# ZD-STM32.net
KiCad netlist of a schematic drawn in Altium Designer
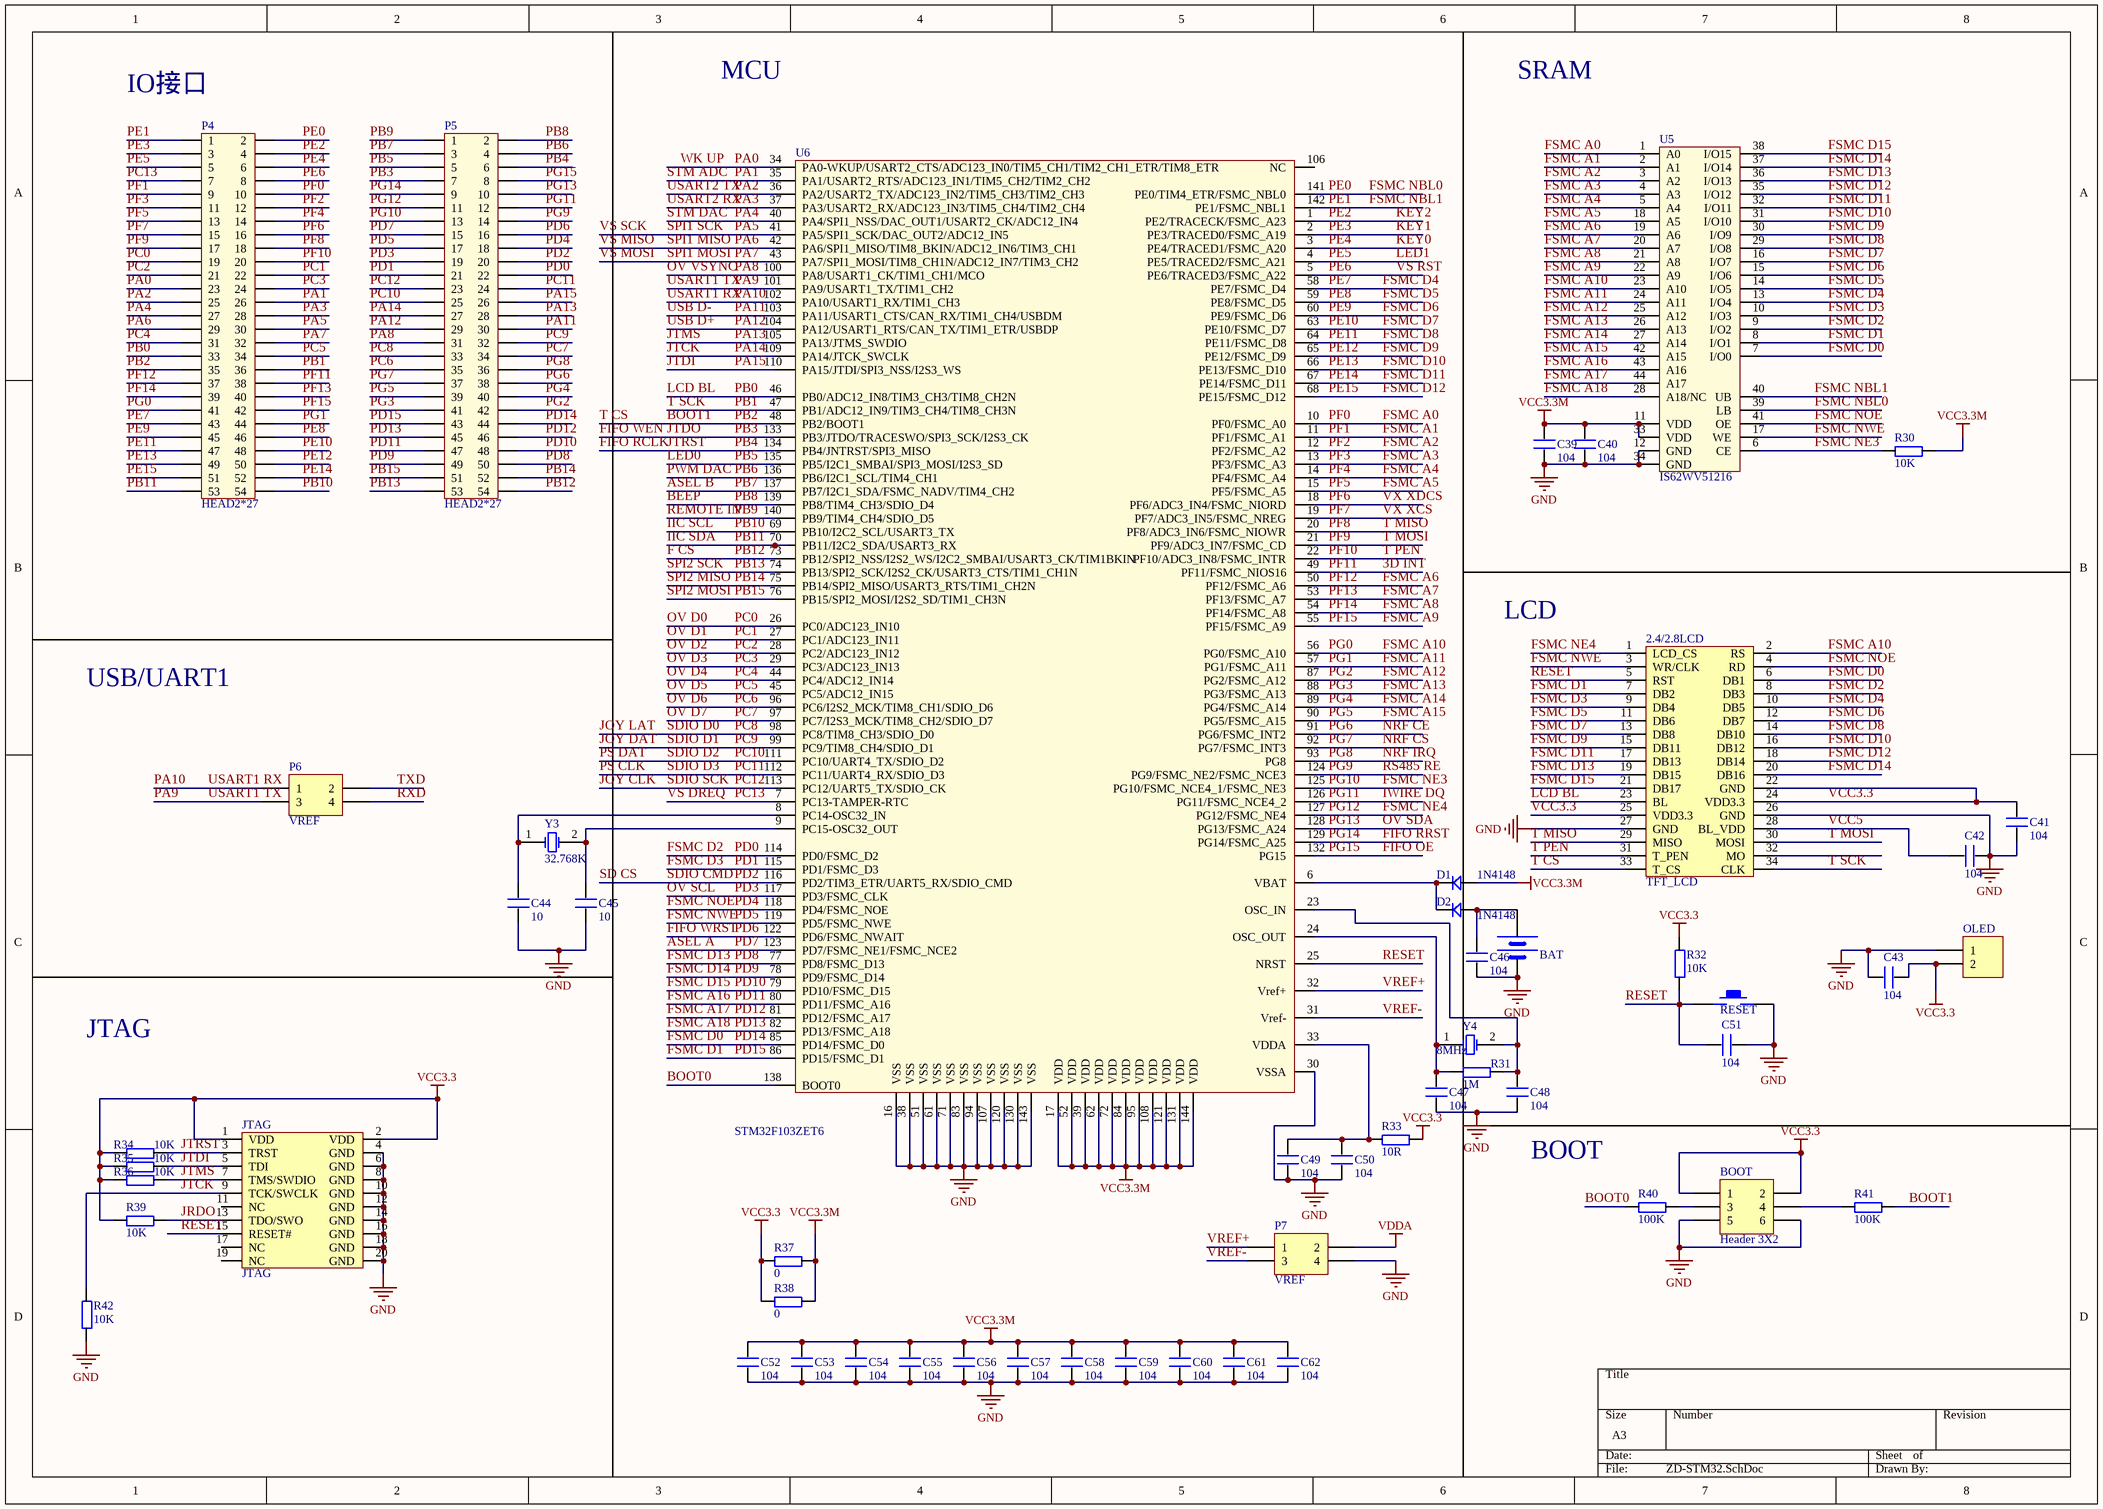
[diagram p0: ZD-STM32.SchDoc]

(export (version "E")
  (design (tool "Eeschema 10.0.6"))
  (components
    (comp (ref "2.4/2.8LCD")
      (value "TFT_LCD")
      (footprint "DB2*17")
      (libsource (lib "液晶模块封装库") (part "TFT_LCD"))
    )
    (comp (ref "BAT") (value "BATT") (footprint "BATM") (libsource (lib "战舰STM32开发板底板封装库") (part "BAT")))
    (comp (ref "BOOT")
      (value "Header 3X2")
      (footprint "HDR2X3")
      (description "Header, 3-Pin, Dual row")
      (fields (field (name "PUBLISHER") "Altium Limited"))
      (libsource (lib "战舰STM32开发板底板封装库") (part "Header 3X2"))
    )
    (comp (ref "C39") (value "104") (footprint "0603P") (libsource (lib "战舰STM32开发板底板封装库") (part "C")))
    (comp (ref "C40") (value "104") (footprint "0603P") (libsource (lib "战舰STM32开发板底板封装库") (part "C")))
    (comp (ref "C41") (value "104") (footprint "0603P") (libsource (lib "战舰STM32开发板底板封装库") (part "C")))
    (comp (ref "C42") (value "104") (footprint "0603P") (libsource (lib "战舰STM32开发板底板封装库") (part "C")))
    (comp (ref "C43") (value "104") (footprint "0603P") (libsource (lib "战舰STM32开发板底板封装库") (part "C")))
    (comp (ref "C44") (value "10") (footprint "0603P") (libsource (lib "战舰STM32开发板底板封装库") (part "C")))
    (comp (ref "C45") (value "10") (footprint "0603P") (libsource (lib "战舰STM32开发板底板封装库") (part "C")))
    (comp (ref "C46") (value "104") (footprint "0603P") (libsource (lib "战舰STM32开发板底板封装库") (part "C")))
    (comp (ref "C47") (value "104") (footprint "0603P") (libsource (lib "战舰STM32开发板底板封装库") (part "C")))
    (comp (ref "C48") (value "104") (footprint "0603P") (libsource (lib "战舰STM32开发板底板封装库") (part "C")))
    (comp (ref "C49") (value "104") (footprint "0603P") (libsource (lib "战舰STM32开发板底板封装库") (part "C")))
    (comp (ref "C50") (value "104") (footprint "0603P") (libsource (lib "战舰STM32开发板底板封装库") (part "C")))
    (comp (ref "C51") (value "104") (footprint "0603P") (libsource (lib "战舰STM32开发板底板封装库") (part "C")))
    (comp (ref "C52") (value "104") (footprint "0603P") (libsource (lib "战舰STM32开发板底板封装库") (part "C")))
    (comp (ref "C53") (value "104") (footprint "0603P") (libsource (lib "战舰STM32开发板底板封装库") (part "C")))
    (comp (ref "C54") (value "104") (footprint "0603P") (libsource (lib "战舰STM32开发板底板封装库") (part "C")))
    (comp (ref "C55") (value "104") (footprint "0603P") (libsource (lib "战舰STM32开发板底板封装库") (part "C")))
    (comp (ref "C56") (value "104") (footprint "0603P") (libsource (lib "战舰STM32开发板底板封装库") (part "C")))
    (comp (ref "C57") (value "104") (footprint "0603P") (libsource (lib "战舰STM32开发板底板封装库") (part "C")))
    (comp (ref "C58") (value "104") (footprint "0603P") (libsource (lib "战舰STM32开发板底板封装库") (part "C")))
    (comp (ref "C59") (value "104") (footprint "0603P") (libsource (lib "战舰STM32开发板底板封装库") (part "C")))
    (comp (ref "C60") (value "104") (footprint "0603P") (libsource (lib "战舰STM32开发板底板封装库") (part "C")))
    (comp (ref "C61") (value "104") (footprint "0603P") (libsource (lib "战舰STM32开发板底板封装库") (part "C")))
    (comp (ref "C62") (value "104") (footprint "0603P") (libsource (lib "战舰STM32开发板底板封装库") (part "C")))
    (comp (ref "D1") (value "1N4148") (footprint "DIODE_SOP") (libsource (lib "战舰STM32开发板底板封装库") (part "D")))
    (comp (ref "D2") (value "1N4148") (footprint "DIODE_SOP") (libsource (lib "战舰STM32开发板底板封装库") (part "D")))
    (comp (ref "JTAG") (value "JTAG") (footprint "JTAG_20") (libsource (lib "战舰STM32开发板底板封装库") (part "JTAG")))
    (comp (ref "OLED")
      (value "MIC/LINE")
      (footprint "HDR1X2")
      (description "Header, 2-Pin")
      (fields (field (name "PUBLISHER") "Altium Limited"))
      (libsource (lib "战舰STM32开发板底板封装库") (part "Header 2_1"))
    )
    (comp (ref "P4")
      (value "HEAD2*27")
      (footprint "HEAD2*27")
      (libsource (lib "战舰STM32开发板底板封装库") (part "HEAD2*27"))
    )
    (comp (ref "P5")
      (value "HEAD2*27")
      (footprint "HEAD2*27")
      (libsource (lib "战舰STM32开发板底板封装库") (part "HEAD2*27"))
    )
    (comp (ref "P6")
      (value "VREF")
      (footprint "HDR2X2")
      (description "Header, 2-Pin, Dual row")
      (fields (field (name "PUBLISHER") "Altium Limited"))
      (libsource (lib "战舰STM32开发板底板封装库") (part "Header 2X2"))
    )
    (comp (ref "P7")
      (value "VREF")
      (footprint "HDR2X2")
      (description "Header, 2-Pin, Dual row")
      (fields (field (name "PUBLISHER") "Altium Limited"))
      (libsource (lib "战舰STM32开发板底板封装库") (part "Header 2X2"))
    )
    (comp (ref "R30") (value "10K") (footprint "0603P") (libsource (lib "战舰STM32开发板底板封装库") (part "R")))
    (comp (ref "R31") (value "1M") (footprint "0603P") (libsource (lib "战舰STM32开发板底板封装库") (part "R")))
    (comp (ref "R32") (value "10K") (footprint "0603P") (libsource (lib "战舰STM32开发板底板封装库") (part "R")))
    (comp (ref "R33") (value "10R") (footprint "0603P") (libsource (lib "战舰STM32开发板底板封装库") (part "R")))
    (comp (ref "R34") (value "10K") (footprint "0603P") (libsource (lib "战舰STM32开发板底板封装库") (part "R")))
    (comp (ref "R35") (value "10K") (footprint "0603P") (libsource (lib "战舰STM32开发板底板封装库") (part "R")))
    (comp (ref "R36") (value "10K") (footprint "0603P") (libsource (lib "战舰STM32开发板底板封装库") (part "R")))
    (comp (ref "R37") (value "0") (footprint "0603P") (libsource (lib "战舰STM32开发板底板封装库") (part "R")))
    (comp (ref "R38") (value "0") (footprint "0603P") (libsource (lib "战舰STM32开发板底板封装库") (part "R")))
    (comp (ref "R39") (value "10K") (footprint "0603P") (libsource (lib "战舰STM32开发板底板封装库") (part "R")))
    (comp (ref "R40") (value "100K") (footprint "0603P") (libsource (lib "战舰STM32开发板底板封装库") (part "R")))
    (comp (ref "R41") (value "100K") (footprint "0603P") (libsource (lib "战舰STM32开发板底板封装库") (part "R")))
    (comp (ref "R42") (value "10K") (footprint "0603P") (libsource (lib "战舰STM32开发板底板封装库") (part "R")))
    (comp (ref "RESET")
      (value "KEY_M")
      (footprint "KEY_M")
      (libsource (lib "战舰STM32开发板底板封装库") (part "KEY_M"))
    )
    (comp (ref "U5")
      (value "IS62WV51216")
      (footprint "TSOP44")
      (libsource (lib "战舰STM32开发板底板封装库") (part "IS61LV51216"))
    )
    (comp (ref "U6")
      (value "STM32F103ZET6")
      (footprint "LQFP144")
      (libsource (lib "战舰STM32开发板底板封装库") (part "STM32F103ZET6"))
    )
    (comp (ref "Y3")
      (value "32.768K")
      (footprint "XTAL32")
      (description "Crystal Oscillator")
      (fields (field (name "PUBLISHER") "Altium Limited"))
      (libsource (lib "战舰STM32开发板底板封装库") (part "XTAL_1"))
    )
    (comp (ref "Y4")
      (value "8MHz")
      (footprint "XTAL_US")
      (description "Crystal Oscillator")
      (fields (field (name "PUBLISHER") "Altium Limited"))
      (libsource (lib "战舰STM32开发板底板封装库") (part "XTAL"))
    )
  )
  (nets
    (net (code "1") (name "/3D INT") (class "Default")
      (node (ref "P4") (pin "38") (pinfunction "38_38") (pintype "passive"))
      (node (ref "U6") (pin "49") (pinfunction "PF11/FSMC_NIOS16_49") (pintype "passive"))
    )
    (net (code "2") (name "/ASEL A") (class "Default")
      (node (ref "P5") (pin "15") (pinfunction "15_15") (pintype "passive"))
      (node (ref "U6") (pin "123") (pinfunction "PD7/FSMC_NE1/FSMC_NCE2_123") (pintype "passive"))
    )
    (net (code "3") (name "/ASEL B") (class "Default")
      (node (ref "P5") (pin "3") (pinfunction "3_3") (pintype "passive"))
      (node (ref "U6") (pin "137") (pinfunction "PB7/I2C1_SDA/FSMC_NADV/TIM4_CH2_137") (pintype "passive"))
    )
    (net (code "4") (name "/BEEP") (class "Default")
      (node (ref "P5") (pin "2") (pinfunction "2_2") (pintype "passive"))
      (node (ref "U6") (pin "139") (pinfunction "PB8/TIM4_CH3/SDIO_D4_139") (pintype "passive"))
    )
    (net (code "5") (name "/BOOT0") (class "Default")
      (node (ref "R40") (pin "1") (pintype "passive"))
      (node (ref "U6") (pin "138") (pinfunction "BOOT0_138") (pintype "passive"))
    )
    (net (code "6") (name "/BOOT1") (class "Default")
      (node (ref "2.4/2.8LCD") (pin "33") (pinfunction "T_CS_33") (pintype "passive"))
      (node (ref "P4") (pin "35") (pinfunction "35_35") (pintype "passive"))
      (node (ref "R41") (pin "2") (pintype "passive"))
      (node (ref "U6") (pin "48") (pinfunction "PB2/BOOT1_48") (pintype "passive"))
    )
    (net (code "7") (name "/F CS") (class "Default")
      (node (ref "P5") (pin "54") (pinfunction "54_54") (pintype "passive"))
      (node (ref "U6") (pin "73") (pinfunction "PB12/SPI2_NSS/I2S2_WS/I2C2_SMBAI/USART3_CK/TIM1BKIN_73") (pintype "passive"))
    )
    (net (code "8") (name "/FIFO OE") (class "Default")
      (node (ref "P5") (pin "8") (pinfunction "8_8") (pintype "passive"))
      (node (ref "U6") (pin "132") (pinfunction "PG15_132") (pintype "passive"))
    )
    (net (code "9") (name "/FIFO RCLK") (class "Default")
      (node (ref "JTAG") (pin "3") (pinfunction "TRST_3") (pintype "passive"))
      (node (ref "P5") (pin "6") (pinfunction "6_6") (pintype "passive"))
      (node (ref "R34") (pin "2") (pintype "passive"))
      (node (ref "U6") (pin "134") (pinfunction "PB4/JNTRST/SPI3_MISO_134") (pintype "passive"))
    )
    (net (code "10") (name "/FIFO RRST") (class "Default")
      (node (ref "P5") (pin "9") (pinfunction "9_9") (pintype "passive"))
      (node (ref "U6") (pin "129") (pinfunction "PG14/FSMC_A25_129") (pintype "passive"))
    )
    (net (code "11") (name "/FIFO WEN") (class "Default")
      (node (ref "P5") (pin "7") (pinfunction "7_7") (pintype "passive"))
      (node (ref "U6") (pin "133") (pinfunction "PB3/JTDO/TRACESWO/SPI3_SCK/I2S3_CK_133") (pintype "passive"))
    )
    (net (code "12") (name "/FIFO WRST") (class "Default")
      (node (ref "P5") (pin "16") (pinfunction "16_16") (pintype "passive"))
      (node (ref "U6") (pin "122") (pinfunction "PD6/FSMC_NWAIT_122") (pintype "passive"))
    )
    (net (code "13") (name "/FSMC A0") (class "Default")
      (node (ref "P4") (pin "10") (pinfunction "10_10") (pintype "passive"))
      (node (ref "U5") (pin "1") (pinfunction "A0_1") (pintype "passive"))
      (node (ref "U6") (pin "10") (pinfunction "PF0/FSMC_A0_10") (pintype "passive"))
    )
    (net (code "14") (name "/FSMC A1") (class "Default")
      (node (ref "P4") (pin "9") (pinfunction "9_9") (pintype "passive"))
      (node (ref "U5") (pin "2") (pinfunction "A1_2") (pintype "passive"))
      (node (ref "U6") (pin "11") (pinfunction "PF1/FSMC_A1_11") (pintype "passive"))
    )
    (net (code "15") (name "/FSMC A2") (class "Default")
      (node (ref "P4") (pin "12") (pinfunction "12_12") (pintype "passive"))
      (node (ref "U5") (pin "3") (pinfunction "A2_3") (pintype "passive"))
      (node (ref "U6") (pin "12") (pinfunction "PF2/FSMC_A2_12") (pintype "passive"))
    )
    (net (code "16") (name "/FSMC A3") (class "Default")
      (node (ref "P4") (pin "11") (pinfunction "11_11") (pintype "passive"))
      (node (ref "U5") (pin "4") (pinfunction "A3_4") (pintype "passive"))
      (node (ref "U6") (pin "13") (pinfunction "PF3/FSMC_A3_13") (pintype "passive"))
    )
    (net (code "17") (name "/FSMC A4") (class "Default")
      (node (ref "P4") (pin "14") (pinfunction "14_14") (pintype "passive"))
      (node (ref "U5") (pin "5") (pinfunction "A4_5") (pintype "passive"))
      (node (ref "U6") (pin "14") (pinfunction "PF4/FSMC_A4_14") (pintype "passive"))
    )
    (net (code "18") (name "/FSMC A5") (class "Default")
      (node (ref "P4") (pin "13") (pinfunction "13_13") (pintype "passive"))
      (node (ref "U5") (pin "18") (pinfunction "A5_18") (pintype "passive"))
      (node (ref "U6") (pin "15") (pinfunction "PF5/FSMC_A5_15") (pintype "passive"))
    )
    (net (code "19") (name "/FSMC A6") (class "Default")
      (node (ref "P4") (pin "37") (pinfunction "37_37") (pintype "passive"))
      (node (ref "U5") (pin "19") (pinfunction "A6_19") (pintype "passive"))
      (node (ref "U6") (pin "50") (pinfunction "PF12/FSMC_A6_50") (pintype "passive"))
    )
    (net (code "20") (name "/FSMC A7") (class "Default")
      (node (ref "P4") (pin "40") (pinfunction "40_40") (pintype "passive"))
      (node (ref "U5") (pin "20") (pinfunction "A7_20") (pintype "passive"))
      (node (ref "U6") (pin "53") (pinfunction "PF13/FSMC_A7_53") (pintype "passive"))
    )
    (net (code "21") (name "/FSMC A8") (class "Default")
      (node (ref "P4") (pin "39") (pinfunction "39_39") (pintype "passive"))
      (node (ref "U5") (pin "21") (pinfunction "A8_21") (pintype "passive"))
      (node (ref "U6") (pin "54") (pinfunction "PF14/FSMC_A8_54") (pintype "passive"))
    )
    (net (code "22") (name "/FSMC A9") (class "Default")
      (node (ref "P4") (pin "42") (pinfunction "42_42") (pintype "passive"))
      (node (ref "U5") (pin "22") (pinfunction "A9_22") (pintype "passive"))
      (node (ref "U6") (pin "55") (pinfunction "PF15/FSMC_A9_55") (pintype "passive"))
    )
    (net (code "23") (name "/FSMC A10") (class "Default")
      (node (ref "2.4/2.8LCD") (pin "2") (pinfunction "RS_2") (pintype "passive"))
      (node (ref "P4") (pin "41") (pinfunction "41_41") (pintype "passive"))
      (node (ref "U5") (pin "23") (pinfunction "A10_23") (pintype "passive"))
      (node (ref "U6") (pin "56") (pinfunction "PG0/FSMC_A10_56") (pintype "passive"))
    )
    (net (code "24") (name "/FSMC A11") (class "Default")
      (node (ref "P4") (pin "44") (pinfunction "44_44") (pintype "passive"))
      (node (ref "U5") (pin "24") (pinfunction "A11_24") (pintype "passive"))
      (node (ref "U6") (pin "57") (pinfunction "PG1/FSMC_A11_57") (pintype "passive"))
    )
    (net (code "25") (name "/FSMC A12") (class "Default")
      (node (ref "P5") (pin "42") (pinfunction "42_42") (pintype "passive"))
      (node (ref "U5") (pin "25") (pinfunction "A12_25") (pintype "passive"))
      (node (ref "U6") (pin "87") (pinfunction "PG2/FSMC_A12_87") (pintype "passive"))
    )
    (net (code "26") (name "/FSMC A13") (class "Default")
      (node (ref "P5") (pin "41") (pinfunction "41_41") (pintype "passive"))
      (node (ref "U5") (pin "26") (pinfunction "A13_26") (pintype "passive"))
      (node (ref "U6") (pin "88") (pinfunction "PG3/FSMC_A13_88") (pintype "passive"))
    )
    (net (code "27") (name "/FSMC A14") (class "Default")
      (node (ref "P5") (pin "40") (pinfunction "40_40") (pintype "passive"))
      (node (ref "U5") (pin "27") (pinfunction "A14_27") (pintype "passive"))
      (node (ref "U6") (pin "89") (pinfunction "PG4/FSMC_A14_89") (pintype "passive"))
    )
    (net (code "28") (name "/FSMC A15") (class "Default")
      (node (ref "P5") (pin "39") (pinfunction "39_39") (pintype "passive"))
      (node (ref "U5") (pin "42") (pinfunction "A15_42") (pintype "passive"))
      (node (ref "U6") (pin "90") (pinfunction "PG5/FSMC_A15_90") (pintype "passive"))
    )
    (net (code "29") (name "/FSMC A16") (class "Default")
      (node (ref "P5") (pin "47") (pinfunction "47_47") (pintype "passive"))
      (node (ref "U5") (pin "43") (pinfunction "A16_43") (pintype "passive"))
      (node (ref "U6") (pin "80") (pinfunction "PD11/FSMC_A16_80") (pintype "passive"))
    )
    (net (code "30") (name "/FSMC A17") (class "Default")
      (node (ref "P5") (pin "46") (pinfunction "46_46") (pintype "passive"))
      (node (ref "U5") (pin "44") (pinfunction "A17_44") (pintype "passive"))
      (node (ref "U6") (pin "81") (pinfunction "PD12/FSMC_A17_81") (pintype "passive"))
    )
    (net (code "31") (name "/FSMC A18") (class "Default")
      (node (ref "P5") (pin "45") (pinfunction "45_45") (pintype "passive"))
      (node (ref "U5") (pin "28") (pinfunction "A18/NC_28") (pintype "passive"))
      (node (ref "U6") (pin "82") (pinfunction "PD13/FSMC_A18_82") (pintype "passive"))
    )
    (net (code "32") (name "/FSMC D0") (class "Default")
      (node (ref "2.4/2.8LCD") (pin "6") (pinfunction "DB1_6") (pintype "passive"))
      (node (ref "P5") (pin "44") (pinfunction "44_44") (pintype "passive"))
      (node (ref "U5") (pin "7") (pinfunction "I/O0_7") (pintype "passive"))
      (node (ref "U6") (pin "85") (pinfunction "PD14/FSMC_D0_85") (pintype "passive"))
    )
    (net (code "33") (name "/FSMC D1") (class "Default")
      (node (ref "2.4/2.8LCD") (pin "7") (pinfunction "DB2_7") (pintype "passive"))
      (node (ref "P5") (pin "43") (pinfunction "43_43") (pintype "passive"))
      (node (ref "U5") (pin "8") (pinfunction "I/O1_8") (pintype "passive"))
      (node (ref "U6") (pin "86") (pinfunction "PD15/FSMC_D1_86") (pintype "passive"))
    )
    (net (code "34") (name "/FSMC D2") (class "Default")
      (node (ref "2.4/2.8LCD") (pin "8") (pinfunction "DB3_8") (pintype "passive"))
      (node (ref "P5") (pin "22") (pinfunction "22_22") (pintype "passive"))
      (node (ref "U5") (pin "9") (pinfunction "I/O2_9") (pintype "passive"))
      (node (ref "U6") (pin "114") (pinfunction "PD0/FSMC_D2_114") (pintype "passive"))
    )
    (net (code "35") (name "/FSMC D3") (class "Default")
      (node (ref "2.4/2.8LCD") (pin "9") (pinfunction "DB4_9") (pintype "passive"))
      (node (ref "P5") (pin "21") (pinfunction "21_21") (pintype "passive"))
      (node (ref "U5") (pin "10") (pinfunction "I/O3_10") (pintype "passive"))
      (node (ref "U6") (pin "115") (pinfunction "PD1/FSMC_D3_115") (pintype "passive"))
    )
    (net (code "36") (name "/FSMC D4") (class "Default")
      (node (ref "2.4/2.8LCD") (pin "10") (pinfunction "DB5_10") (pintype "passive"))
      (node (ref "P4") (pin "43") (pinfunction "43_43") (pintype "passive"))
      (node (ref "U5") (pin "13") (pinfunction "I/O4_13") (pintype "passive"))
      (node (ref "U6") (pin "58") (pinfunction "PE7/FSMC_D4_58") (pintype "passive"))
    )
    (net (code "37") (name "/FSMC D5") (class "Default")
      (node (ref "2.4/2.8LCD") (pin "11") (pinfunction "DB6_11") (pintype "passive"))
      (node (ref "P4") (pin "46") (pinfunction "46_46") (pintype "passive"))
      (node (ref "U5") (pin "14") (pinfunction "I/O5_14") (pintype "passive"))
      (node (ref "U6") (pin "59") (pinfunction "PE8/FSMC_D5_59") (pintype "passive"))
    )
    (net (code "38") (name "/FSMC D6") (class "Default")
      (node (ref "2.4/2.8LCD") (pin "12") (pinfunction "DB7_12") (pintype "passive"))
      (node (ref "P4") (pin "45") (pinfunction "45_45") (pintype "passive"))
      (node (ref "U5") (pin "15") (pinfunction "I/O6_15") (pintype "passive"))
      (node (ref "U6") (pin "60") (pinfunction "PE9/FSMC_D6_60") (pintype "passive"))
    )
    (net (code "39") (name "/FSMC D7") (class "Default")
      (node (ref "2.4/2.8LCD") (pin "13") (pinfunction "DB8_13") (pintype "passive"))
      (node (ref "P4") (pin "48") (pinfunction "48_48") (pintype "passive"))
      (node (ref "U5") (pin "16") (pinfunction "I/O7_16") (pintype "passive"))
      (node (ref "U6") (pin "63") (pinfunction "PE10/FSMC_D7_63") (pintype "passive"))
    )
    (net (code "40") (name "/FSMC D8") (class "Default")
      (node (ref "2.4/2.8LCD") (pin "14") (pinfunction "DB10_14") (pintype "passive"))
      (node (ref "P4") (pin "47") (pinfunction "47_47") (pintype "passive"))
      (node (ref "U5") (pin "29") (pinfunction "I/O8_29") (pintype "passive"))
      (node (ref "U6") (pin "64") (pinfunction "PE11/FSMC_D8_64") (pintype "passive"))
    )
    (net (code "41") (name "/FSMC D9") (class "Default")
      (node (ref "2.4/2.8LCD") (pin "15") (pinfunction "DB11_15") (pintype "passive"))
      (node (ref "P4") (pin "50") (pinfunction "50_50") (pintype "passive"))
      (node (ref "U5") (pin "30") (pinfunction "I/O9_30") (pintype "passive"))
      (node (ref "U6") (pin "65") (pinfunction "PE12/FSMC_D9_65") (pintype "passive"))
    )
    (net (code "42") (name "/FSMC D10") (class "Default")
      (node (ref "2.4/2.8LCD") (pin "16") (pinfunction "DB12_16") (pintype "passive"))
      (node (ref "P4") (pin "49") (pinfunction "49_49") (pintype "passive"))
      (node (ref "U5") (pin "31") (pinfunction "I/O10_31") (pintype "passive"))
      (node (ref "U6") (pin "66") (pinfunction "PE13/FSMC_D10_66") (pintype "passive"))
    )
    (net (code "43") (name "/FSMC D11") (class "Default")
      (node (ref "2.4/2.8LCD") (pin "17") (pinfunction "DB13_17") (pintype "passive"))
      (node (ref "P4") (pin "52") (pinfunction "52_52") (pintype "passive"))
      (node (ref "U5") (pin "32") (pinfunction "I/O11_32") (pintype "passive"))
      (node (ref "U6") (pin "67") (pinfunction "PE14/FSMC_D11_67") (pintype "passive"))
    )
    (net (code "44") (name "/FSMC D12") (class "Default")
      (node (ref "2.4/2.8LCD") (pin "18") (pinfunction "DB14_18") (pintype "passive"))
      (node (ref "P4") (pin "51") (pinfunction "51_51") (pintype "passive"))
      (node (ref "U5") (pin "35") (pinfunction "I/O12_35") (pintype "passive"))
      (node (ref "U6") (pin "68") (pinfunction "PE15/FSMC_D12_68") (pintype "passive"))
    )
    (net (code "45") (name "/FSMC D13") (class "Default")
      (node (ref "2.4/2.8LCD") (pin "19") (pinfunction "DB15_19") (pintype "passive"))
      (node (ref "P5") (pin "50") (pinfunction "50_50") (pintype "passive"))
      (node (ref "U5") (pin "36") (pinfunction "I/O13_36") (pintype "passive"))
      (node (ref "U6") (pin "77") (pinfunction "PD8/FSMC_D13_77") (pintype "passive"))
    )
    (net (code "46") (name "/FSMC D14") (class "Default")
      (node (ref "2.4/2.8LCD") (pin "20") (pinfunction "DB16_20") (pintype "passive"))
      (node (ref "P5") (pin "49") (pinfunction "49_49") (pintype "passive"))
      (node (ref "U5") (pin "37") (pinfunction "I/O14_37") (pintype "passive"))
      (node (ref "U6") (pin "78") (pinfunction "PD9/FSMC_D14_78") (pintype "passive"))
    )
    (net (code "47") (name "/FSMC D15") (class "Default")
      (node (ref "2.4/2.8LCD") (pin "21") (pinfunction "DB17_21") (pintype "passive"))
      (node (ref "P5") (pin "48") (pinfunction "48_48") (pintype "passive"))
      (node (ref "U5") (pin "38") (pinfunction "I/O15_38") (pintype "passive"))
      (node (ref "U6") (pin "79") (pinfunction "PD10/FSMC_D15_79") (pintype "passive"))
    )
    (net (code "48") (name "/FSMC NBL0") (class "Default")
      (node (ref "P4") (pin "2") (pinfunction "2_2") (pintype "passive"))
      (node (ref "U5") (pin "39") (pinfunction "LB_39") (pintype "passive"))
      (node (ref "U6") (pin "141") (pinfunction "PE0/TIM4_ETR/FSMC_NBL0_141") (pintype "passive"))
    )
    (net (code "49") (name "/FSMC NBL1") (class "Default")
      (node (ref "P4") (pin "1") (pinfunction "1_1") (pintype "passive"))
      (node (ref "U5") (pin "40") (pinfunction "UB_40") (pintype "passive"))
      (node (ref "U6") (pin "142") (pinfunction "PE1/FSMC_NBL1_142") (pintype "passive"))
    )
    (net (code "50") (name "/FSMC NE3") (class "Default")
      (node (ref "P5") (pin "13") (pinfunction "13_13") (pintype "passive"))
      (node (ref "R30") (pin "1") (pintype "passive"))
      (node (ref "U5") (pin "6") (pinfunction "CE_6") (pintype "passive"))
      (node (ref "U6") (pin "125") (pinfunction "PG10/FSMC_NCE4_1/FSMC_NE3_125") (pintype "passive"))
    )
    (net (code "51") (name "/FSMC NE4") (class "Default")
      (node (ref "2.4/2.8LCD") (pin "1") (pinfunction "LCD_CS_1") (pintype "passive"))
      (node (ref "P5") (pin "11") (pinfunction "11_11") (pintype "passive"))
      (node (ref "U6") (pin "127") (pinfunction "PG12/FSMC_NE4_127") (pintype "passive"))
    )
    (net (code "52") (name "/FSMC NOE") (class "Default")
      (node (ref "2.4/2.8LCD") (pin "4") (pinfunction "RD_4") (pintype "passive"))
      (node (ref "P5") (pin "18") (pinfunction "18_18") (pintype "passive"))
      (node (ref "U5") (pin "41") (pinfunction "OE_41") (pintype "passive"))
      (node (ref "U6") (pin "118") (pinfunction "PD4/FSMC_NOE_118") (pintype "passive"))
    )
    (net (code "53") (name "/FSMC NWE") (class "Default")
      (node (ref "2.4/2.8LCD") (pin "3") (pinfunction "WR/CLK_3") (pintype "passive"))
      (node (ref "P5") (pin "17") (pinfunction "17_17") (pintype "passive"))
      (node (ref "U5") (pin "17") (pinfunction "WE_17") (pintype "passive"))
      (node (ref "U6") (pin "119") (pinfunction "PD5/FSMC_NWE_119") (pintype "passive"))
    )
    (net (code "54") (name "/IIC SCL") (class "Default")
      (node (ref "P4") (pin "54") (pinfunction "54_54") (pintype "passive"))
      (node (ref "U6") (pin "69") (pinfunction "PB10/I2C2_SCL/USART3_TX_69") (pintype "passive"))
    )
    (net (code "55") (name "/IIC SDA") (class "Default")
      (node (ref "P4") (pin "53") (pinfunction "53_53") (pintype "passive"))
      (node (ref "U6") (pin "70") (pinfunction "PB11/I2C2_SDA/USART3_RX_70") (pintype "passive"))
    )
    (net (code "56") (name "/IWIRE DQ") (class "Default")
      (node (ref "P5") (pin "12") (pinfunction "12_12") (pintype "passive"))
      (node (ref "U6") (pin "126") (pinfunction "PG11/FSMC_NCE4_2_126") (pintype "passive"))
    )
    (net (code "57") (name "/JOY CLK") (class "Default")
      (node (ref "P5") (pin "23") (pinfunction "23_23") (pintype "passive"))
      (node (ref "U6") (pin "113") (pinfunction "PC12/UART5_TX/SDIO_CK_113") (pintype "passive"))
    )
    (net (code "58") (name "/JOY DAT") (class "Default")
      (node (ref "P5") (pin "32") (pinfunction "32_32") (pintype "passive"))
      (node (ref "U6") (pin "99") (pinfunction "PC9/TIM8_CH4/SDIO_D1_99") (pintype "passive"))
    )
    (net (code "59") (name "/JOY LAT") (class "Default")
      (node (ref "P5") (pin "33") (pinfunction "33_33") (pintype "passive"))
      (node (ref "U6") (pin "98") (pinfunction "PC8/TIM8_CH3/SDIO_D0_98") (pintype "passive"))
    )
    (net (code "60") (name "/JRDO") (class "Default")
      (node (ref "JTAG") (pin "13") (pinfunction "TDO/SWO_13") (pintype "passive"))
      (node (ref "R39") (pin "2") (pintype "passive"))
    )
    (net (code "61") (name "/JTCK") (class "Default")
      (node (ref "JTAG") (pin "9") (pinfunction "TCK/SWCLK_9") (pintype "passive"))
      (node (ref "P5") (pin "27") (pinfunction "27_27") (pintype "passive"))
      (node (ref "R42") (pin "2") (pintype "passive"))
      (node (ref "U6") (pin "109") (pinfunction "PA14/JTCK_SWCLK_109") (pintype "passive"))
    )
    (net (code "62") (name "/JTDI") (class "Default")
      (node (ref "JTAG") (pin "5") (pinfunction "TDI_5") (pintype "passive"))
      (node (ref "P5") (pin "26") (pinfunction "26_26") (pintype "passive"))
      (node (ref "R35") (pin "2") (pintype "passive"))
      (node (ref "U6") (pin "110") (pinfunction "PA15/JTDI/SPI3_NSS/I2S3_WS_110") (pintype "passive"))
    )
    (net (code "63") (name "/JTMS") (class "Default")
      (node (ref "JTAG") (pin "7") (pinfunction "TMS/SWDIO_7") (pintype "passive"))
      (node (ref "P5") (pin "28") (pinfunction "28_28") (pintype "passive"))
      (node (ref "R36") (pin "2") (pintype "passive"))
      (node (ref "U6") (pin "105") (pinfunction "PA13/JTMS_SWDIO_105") (pintype "passive"))
    )
    (net (code "64") (name "/KEY0") (class "Default")
      (node (ref "P4") (pin "6") (pinfunction "6_6") (pintype "passive"))
      (node (ref "U6") (pin "3") (pinfunction "PE4/TRACED1/FSMC_A20_3") (pintype "passive"))
    )
    (net (code "65") (name "/KEY1") (class "Default")
      (node (ref "P4") (pin "3") (pinfunction "3_3") (pintype "passive"))
      (node (ref "U6") (pin "2") (pinfunction "PE3/TRACED0/FSMC_A19_2") (pintype "passive"))
    )
    (net (code "66") (name "/KEY2") (class "Default")
      (node (ref "P4") (pin "4") (pinfunction "4_4") (pintype "passive"))
      (node (ref "U6") (pin "1") (pinfunction "PE2/TRACECK/FSMC_A23_1") (pintype "passive"))
    )
    (net (code "67") (name "/LCD BL") (class "Default")
      (node (ref "2.4/2.8LCD") (pin "23") (pinfunction "BL_23") (pintype "passive"))
      (node (ref "P4") (pin "33") (pinfunction "33_33") (pintype "passive"))
      (node (ref "U6") (pin "46") (pinfunction "PB0/ADC12_IN8/TIM3_CH3/TIM8_CH2N_46") (pintype "passive"))
    )
    (net (code "68") (name "/LED0") (class "Default")
      (node (ref "P5") (pin "5") (pinfunction "5_5") (pintype "passive"))
      (node (ref "U6") (pin "135") (pinfunction "PB5/I2C1_SMBAI/SPI3_MOSI/I2S3_SD_135") (pintype "passive"))
    )
    (net (code "69") (name "/LED1") (class "Default")
      (node (ref "P4") (pin "5") (pinfunction "5_5") (pintype "passive"))
      (node (ref "U6") (pin "4") (pinfunction "PE5/TRACED2/FSMC_A21_4") (pintype "passive"))
    )
    (net (code "70") (name "/NRF CE") (class "Default")
      (node (ref "P5") (pin "38") (pinfunction "38_38") (pintype "passive"))
      (node (ref "U6") (pin "91") (pinfunction "PG6/FSMC_INT2_91") (pintype "passive"))
    )
    (net (code "71") (name "/NRF CS") (class "Default")
      (node (ref "P5") (pin "37") (pinfunction "37_37") (pintype "passive"))
      (node (ref "U6") (pin "92") (pinfunction "PG7/FSMC_INT3_92") (pintype "passive"))
    )
    (net (code "72") (name "/NRF IRQ") (class "Default")
      (node (ref "P5") (pin "36") (pinfunction "36_36") (pintype "passive"))
      (node (ref "U6") (pin "93") (pinfunction "PG8_93") (pintype "passive"))
    )
    (net (code "73") (name "/OV D0") (class "Default")
      (node (ref "P4") (pin "19") (pinfunction "19_19") (pintype "passive"))
      (node (ref "U6") (pin "26") (pinfunction "PC0/ADC123_IN10_26") (pintype "passive"))
    )
    (net (code "74") (name "/OV D1") (class "Default")
      (node (ref "P4") (pin "22") (pinfunction "22_22") (pintype "passive"))
      (node (ref "U6") (pin "27") (pinfunction "PC1/ADC123_IN11_27") (pintype "passive"))
    )
    (net (code "75") (name "/OV D2") (class "Default")
      (node (ref "P4") (pin "21") (pinfunction "21_21") (pintype "passive"))
      (node (ref "U6") (pin "28") (pinfunction "PC2/ADC123_IN12_28") (pintype "passive"))
    )
    (net (code "76") (name "/OV D3") (class "Default")
      (node (ref "P4") (pin "24") (pinfunction "24_24") (pintype "passive"))
      (node (ref "U6") (pin "29") (pinfunction "PC3/ADC123_IN13_29") (pintype "passive"))
    )
    (net (code "77") (name "/OV D4") (class "Default")
      (node (ref "P4") (pin "31") (pinfunction "31_31") (pintype "passive"))
      (node (ref "U6") (pin "44") (pinfunction "PC4/ADC12_IN14_44") (pintype "passive"))
    )
    (net (code "78") (name "/OV D5") (class "Default")
      (node (ref "P4") (pin "34") (pinfunction "34_34") (pintype "passive"))
      (node (ref "U6") (pin "45") (pinfunction "PC5/ADC12_IN15_45") (pintype "passive"))
    )
    (net (code "79") (name "/OV D6") (class "Default")
      (node (ref "P5") (pin "35") (pinfunction "35_35") (pintype "passive"))
      (node (ref "U6") (pin "96") (pinfunction "PC6/I2S2_MCK/TIM8_CH1/SDIO_D6_96") (pintype "passive"))
    )
    (net (code "80") (name "/OV D7") (class "Default")
      (node (ref "P5") (pin "34") (pinfunction "34_34") (pintype "passive"))
      (node (ref "U6") (pin "97") (pinfunction "PC7/I2S3_MCK/TIM8_CH2/SDIO_D7_97") (pintype "passive"))
    )
    (net (code "81") (name "/OV SCL") (class "Default")
      (node (ref "P5") (pin "19") (pinfunction "19_19") (pintype "passive"))
      (node (ref "U6") (pin "117") (pinfunction "PD3/FSMC_CLK_117") (pintype "passive"))
    )
    (net (code "82") (name "/OV SDA") (class "Default")
      (node (ref "P5") (pin "10") (pinfunction "10_10") (pintype "passive"))
      (node (ref "U6") (pin "128") (pinfunction "PG13/FSMC_A24_128") (pintype "passive"))
    )
    (net (code "83") (name "/OV VSYNC") (class "Default")
      (node (ref "P5") (pin "31") (pinfunction "31_31") (pintype "passive"))
      (node (ref "U6") (pin "100") (pinfunction "PA8/USART1_CK/TIM1_CH1/MCO_100") (pintype "passive"))
    )
    (net (code "84") (name "/PA0") (class "Default")
      (node (ref "P4") (pin "23") (pinfunction "23_23") (pintype "passive"))
      (node (ref "U6") (pin "34") (pinfunction "PA0-WKUP/USART2_CTS/ADC123_IN0/TIM5_CH1/TIM2_CH1_ETR/TIM8_ETR_34") (pintype "passive"))
    )
    (net (code "85") (name "/PA1") (class "Default")
      (node (ref "P4") (pin "26") (pinfunction "26_26") (pintype "passive"))
      (node (ref "U6") (pin "35") (pinfunction "PA1/USART2_RTS/ADC123_IN1/TIM5_CH2/TIM2_CH2_35") (pintype "passive"))
    )
    (net (code "86") (name "/PA2") (class "Default")
      (node (ref "P4") (pin "25") (pinfunction "25_25") (pintype "passive"))
      (node (ref "U6") (pin "36") (pinfunction "PA2/USART2_TX/ADC123_IN2/TIM5_CH3/TIM2_CH3_36") (pintype "passive"))
    )
    (net (code "87") (name "/PA3") (class "Default")
      (node (ref "P4") (pin "28") (pinfunction "28_28") (pintype "passive"))
      (node (ref "U6") (pin "37") (pinfunction "PA3/USART2_RX/ADC123_IN3/TIM5_CH4/TIM2_CH4_37") (pintype "passive"))
    )
    (net (code "88") (name "/PA4") (class "Default")
      (node (ref "P4") (pin "27") (pinfunction "27_27") (pintype "passive"))
      (node (ref "U6") (pin "40") (pinfunction "PA4/SPI1_NSS/DAC_OUT1/USART2_CK/ADC12_IN4_40") (pintype "passive"))
    )
    (net (code "89") (name "/PA5") (class "Default")
      (node (ref "P4") (pin "30") (pinfunction "30_30") (pintype "passive"))
      (node (ref "U6") (pin "41") (pinfunction "PA5/SPI1_SCK/DAC_OUT2/ADC12_IN5_41") (pintype "passive"))
    )
    (net (code "90") (name "/PA6") (class "Default")
      (node (ref "P4") (pin "29") (pinfunction "29_29") (pintype "passive"))
      (node (ref "U6") (pin "42") (pinfunction "PA6/SPI1_MISO/TIM8_BKIN/ADC12_IN6/TIM3_CH1_42") (pintype "passive"))
    )
    (net (code "91") (name "/PA7") (class "Default")
      (node (ref "P4") (pin "32") (pinfunction "32_32") (pintype "passive"))
      (node (ref "U6") (pin "43") (pinfunction "PA7/SPI1_MOSI/TIM8_CH1N/ADC12_IN7/TIM3_CH2_43") (pintype "passive"))
    )
    (net (code "92") (name "/PA9") (class "Default")
      (node (ref "P6") (pin "3") (pinfunction "3_3") (pintype "passive"))
      (node (ref "U6") (pin "101") (pinfunction "PA9/USART1_TX/TIM1_CH2_101") (pintype "passive"))
    )
    (net (code "93") (name "/PA10") (class "Default")
      (node (ref "P6") (pin "1") (pinfunction "1_1") (pintype "passive"))
      (node (ref "U6") (pin "102") (pinfunction "PA10/USART1_RX/TIM1_CH3_102") (pintype "passive"))
    )
    (net (code "94") (name "/PA11") (class "Default")
      (node (ref "P5") (pin "30") (pinfunction "30_30") (pintype "passive"))
      (node (ref "U6") (pin "103") (pinfunction "PA11/USART1_CTS/CAN_RX/TIM1_CH4/USBDM_103") (pintype "passive"))
    )
    (net (code "95") (name "/PA12") (class "Default")
      (node (ref "P5") (pin "29") (pinfunction "29_29") (pintype "passive"))
      (node (ref "U6") (pin "104") (pinfunction "PA12/USART1_RTS/CAN_TX/TIM1_ETR/USBDP_104") (pintype "passive"))
    )
    (net (code "96") (name "/PB1") (class "Default")
      (node (ref "2.4/2.8LCD") (pin "34") (pinfunction "CLK_34") (pintype "passive"))
      (node (ref "P4") (pin "36") (pinfunction "36_36") (pintype "passive"))
      (node (ref "U6") (pin "47") (pinfunction "PB1/ADC12_IN9/TIM3_CH4/TIM8_CH3N_47") (pintype "passive"))
    )
    (net (code "97") (name "/PB6") (class "Default")
      (node (ref "P5") (pin "4") (pinfunction "4_4") (pintype "passive"))
      (node (ref "U6") (pin "136") (pinfunction "PB6/I2C1_SCL/TIM4_CH1_136") (pintype "passive"))
    )
    (net (code "98") (name "/PB9") (class "Default")
      (node (ref "P5") (pin "1") (pinfunction "1_1") (pintype "passive"))
      (node (ref "U6") (pin "140") (pinfunction "PB9/TIM4_CH4/SDIO_D5_140") (pintype "passive"))
    )
    (net (code "99") (name "/PB13") (class "Default")
      (node (ref "P5") (pin "53") (pinfunction "53_53") (pintype "passive"))
      (node (ref "U6") (pin "74") (pinfunction "PB13/SPI2_SCK/I2S2_CK/USART3_CTS/TIM1_CH1N_74") (pintype "passive"))
    )
    (net (code "100") (name "/PB14") (class "Default")
      (node (ref "P5") (pin "52") (pinfunction "52_52") (pintype "passive"))
      (node (ref "U6") (pin "75") (pinfunction "PB14/SPI2_MISO/USART3_RTS/TIM1_CH2N_75") (pintype "passive"))
    )
    (net (code "101") (name "/PB15") (class "Default")
      (node (ref "P5") (pin "51") (pinfunction "51_51") (pintype "passive"))
      (node (ref "U6") (pin "76") (pinfunction "PB15/SPI2_MOSI/I2S2_SD/TIM1_CH3N_76") (pintype "passive"))
    )
    (net (code "102") (name "/PC10") (class "Default")
      (node (ref "P5") (pin "25") (pinfunction "25_25") (pintype "passive"))
      (node (ref "U6") (pin "111") (pinfunction "PC10/UART4_TX/SDIO_D2_111") (pintype "passive"))
    )
    (net (code "103") (name "/PC11") (class "Default")
      (node (ref "P5") (pin "24") (pinfunction "24_24") (pintype "passive"))
      (node (ref "U6") (pin "112") (pinfunction "PC11/UART4_RX/SDIO_D3_112") (pintype "passive"))
    )
    (net (code "104") (name "/PC13") (class "Default")
      (node (ref "P4") (pin "7") (pinfunction "7_7") (pintype "passive"))
      (node (ref "U6") (pin "7") (pinfunction "PC13-TAMPER-RTC_7") (pintype "passive"))
    )
    (net (code "105") (name "/PD2") (class "Default")
      (node (ref "P5") (pin "20") (pinfunction "20_20") (pintype "passive"))
      (node (ref "U6") (pin "116") (pinfunction "PD2/TIM3_ETR/UART5_RX/SDIO_CMD_116") (pintype "passive"))
    )
    (net (code "106") (name "/PE6") (class "Default")
      (node (ref "P4") (pin "8") (pinfunction "8_8") (pintype "passive"))
      (node (ref "U6") (pin "5") (pinfunction "PE6/TRACED3/FSMC_A22_5") (pintype "passive"))
    )
    (net (code "107") (name "/PF6") (class "Default")
      (node (ref "P4") (pin "16") (pinfunction "16_16") (pintype "passive"))
      (node (ref "U6") (pin "18") (pinfunction "PF6/ADC3_IN4/FSMC_NIORD_18") (pintype "passive"))
    )
    (net (code "108") (name "/PF7") (class "Default")
      (node (ref "P4") (pin "15") (pinfunction "15_15") (pintype "passive"))
      (node (ref "U6") (pin "19") (pinfunction "PF7/ADC3_IN5/FSMC_NREG_19") (pintype "passive"))
    )
    (net (code "109") (name "/PF8") (class "Default")
      (node (ref "2.4/2.8LCD") (pin "29") (pinfunction "MISO_29") (pintype "passive"))
      (node (ref "P4") (pin "18") (pinfunction "18_18") (pintype "passive"))
      (node (ref "U6") (pin "20") (pinfunction "PF8/ADC3_IN6/FSMC_NIOWR_20") (pintype "passive"))
    )
    (net (code "110") (name "/PF9") (class "Default")
      (node (ref "2.4/2.8LCD") (pin "30") (pinfunction "MOSI_30") (pintype "passive"))
      (node (ref "P4") (pin "17") (pinfunction "17_17") (pintype "passive"))
      (node (ref "U6") (pin "21") (pinfunction "PF9/ADC3_IN7/FSMC_CD_21") (pintype "passive"))
    )
    (net (code "111") (name "/PF10") (class "Default")
      (node (ref "2.4/2.8LCD") (pin "31") (pinfunction "T_PEN_31") (pintype "passive"))
      (node (ref "P4") (pin "20") (pinfunction "20_20") (pintype "passive"))
      (node (ref "U6") (pin "22") (pinfunction "PF10/ADC3_IN8/FSMC_INTR_22") (pintype "passive"))
    )
    (net (code "112") (name "/PG9") (class "Default")
      (node (ref "P5") (pin "14") (pinfunction "14_14") (pintype "passive"))
      (node (ref "U6") (pin "124") (pinfunction "PG9/FSMC_NE2/FSMC_NCE3_124") (pintype "passive"))
    )
    (net (code "113") (name "/RESET") (class "Default")
      (node (ref "2.4/2.8LCD") (pin "5") (pinfunction "RST_5") (pintype "passive"))
      (node (ref "C51") (pin "2") (pintype "passive"))
      (node (ref "JTAG") (pin "15") (pinfunction "RESET#_15") (pintype "passive"))
      (node (ref "R32") (pin "1") (pintype "passive"))
      (node (ref "RESET") (pin "1") (pinfunction "1_1") (pintype "passive"))
      (node (ref "U6") (pin "25") (pinfunction "NRST_25") (pintype "passive"))
    )
    (net (code "114") (name "/RXD") (class "Default")
      (node (ref "P6") (pin "4") (pinfunction "4_4") (pintype "passive"))
    )
    (net (code "115") (name "/TXD") (class "Default")
      (node (ref "P6") (pin "2") (pinfunction "2_2") (pintype "passive"))
    )
    (net (code "116") (name "/VCC5") (class "Default")
      (node (ref "2.4/2.8LCD") (pin "28") (pinfunction "BL_VDD_28") (pintype "passive"))
      (node (ref "C42") (pin "2") (pintype "passive"))
    )
    (net (code "117") (name "/VREF+") (class "Default")
      (node (ref "P7") (pin "1") (pinfunction "1_1") (pintype "passive"))
      (node (ref "U6") (pin "32") (pinfunction "Vref+_32") (pintype "passive"))
    )
    (net (code "118") (name "/VREF-") (class "Default")
      (node (ref "P7") (pin "3") (pinfunction "3_3") (pintype "passive"))
      (node (ref "U6") (pin "31") (pinfunction "Vref-_31") (pintype "passive"))
    )
    (net (code "119") (name "GND") (class "Default")
      (node (ref "2.4/2.8LCD") (pin "26") (pinfunction "GND_26") (pintype "passive"))
      (node (ref "2.4/2.8LCD") (pin "27") (pinfunction "GND_27") (pintype "passive"))
      (node (ref "BAT") (pin "2") (pinfunction "GND_2") (pintype "passive"))
      (node (ref "BOOT") (pin "5") (pinfunction "5_5") (pintype "passive"))
      (node (ref "BOOT") (pin "6") (pinfunction "6_6") (pintype "passive"))
      (node (ref "C39") (pin "1") (pintype "passive"))
      (node (ref "C40") (pin "1") (pintype "passive"))
      (node (ref "C41") (pin "1") (pintype "passive"))
      (node (ref "C42") (pin "1") (pintype "passive"))
      (node (ref "C43") (pin "2") (pintype "passive"))
      (node (ref "C44") (pin "1") (pintype "passive"))
      (node (ref "C45") (pin "1") (pintype "passive"))
      (node (ref "C46") (pin "1") (pintype "passive"))
      (node (ref "C47") (pin "1") (pintype "passive"))
      (node (ref "C48") (pin "1") (pintype "passive"))
      (node (ref "C49") (pin "1") (pintype "passive"))
      (node (ref "C50") (pin "1") (pintype "passive"))
      (node (ref "C51") (pin "1") (pintype "passive"))
      (node (ref "C52") (pin "2") (pintype "passive"))
      (node (ref "C53") (pin "2") (pintype "passive"))
      (node (ref "C54") (pin "2") (pintype "passive"))
      (node (ref "C55") (pin "2") (pintype "passive"))
      (node (ref "C56") (pin "2") (pintype "passive"))
      (node (ref "C57") (pin "2") (pintype "passive"))
      (node (ref "C58") (pin "2") (pintype "passive"))
      (node (ref "C59") (pin "2") (pintype "passive"))
      (node (ref "C60") (pin "2") (pintype "passive"))
      (node (ref "C61") (pin "2") (pintype "passive"))
      (node (ref "C62") (pin "2") (pintype "passive"))
      (node (ref "JTAG") (pin "10") (pinfunction "GND_10") (pintype "passive"))
      (node (ref "JTAG") (pin "12") (pinfunction "GND_12") (pintype "passive"))
      (node (ref "JTAG") (pin "14") (pinfunction "GND_14") (pintype "passive"))
      (node (ref "JTAG") (pin "16") (pinfunction "GND_16") (pintype "passive"))
      (node (ref "JTAG") (pin "18") (pinfunction "GND_18") (pintype "passive"))
      (node (ref "JTAG") (pin "20") (pinfunction "GND_20") (pintype "passive"))
      (node (ref "JTAG") (pin "4") (pinfunction "GND_4") (pintype "passive"))
      (node (ref "JTAG") (pin "6") (pinfunction "GND_6") (pintype "passive"))
      (node (ref "JTAG") (pin "8") (pinfunction "GND_8") (pintype "passive"))
      (node (ref "OLED") (pin "1") (pinfunction "1_1") (pintype "passive"))
      (node (ref "P7") (pin "4") (pinfunction "4_4") (pintype "passive"))
      (node (ref "R42") (pin "1") (pintype "passive"))
      (node (ref "RESET") (pin "2") (pinfunction "2_2") (pintype "passive"))
      (node (ref "U5") (pin "12") (pinfunction "GND_12") (pintype "passive"))
      (node (ref "U5") (pin "34") (pinfunction "GND_34") (pintype "passive"))
      (node (ref "U6") (pin "107") (pinfunction "VSS_107") (pintype "passive"))
      (node (ref "U6") (pin "120") (pinfunction "VSS_120") (pintype "passive"))
      (node (ref "U6") (pin "130") (pinfunction "VSS_130") (pintype "passive"))
      (node (ref "U6") (pin "143") (pinfunction "VSS_143") (pintype "passive"))
      (node (ref "U6") (pin "16") (pinfunction "VSS_16") (pintype "passive"))
      (node (ref "U6") (pin "30") (pinfunction "VSSA_30") (pintype "passive"))
      (node (ref "U6") (pin "38") (pinfunction "VSS_38") (pintype "passive"))
      (node (ref "U6") (pin "51") (pinfunction "VSS_51") (pintype "passive"))
      (node (ref "U6") (pin "61") (pinfunction "VSS_61") (pintype "passive"))
      (node (ref "U6") (pin "71") (pinfunction "VSS_71") (pintype "passive"))
      (node (ref "U6") (pin "83") (pinfunction "VSS_83") (pintype "passive"))
      (node (ref "U6") (pin "94") (pinfunction "VSS_94") (pintype "passive"))
    )
    (net (code "120") (name "Net-(BAT-VCC)") (class "Default")
      (node (ref "BAT") (pin "1") (pinfunction "VCC_1") (pintype "passive"))
      (node (ref "C46") (pin "2") (pintype "passive"))
      (node (ref "D2") (pin "1") (pintype "passive"))
    )
    (net (code "121") (name "Net-(BOOT-Pad3)") (class "Default")
      (node (ref "BOOT") (pin "3") (pinfunction "3_3") (pintype "passive"))
      (node (ref "R40") (pin "2") (pintype "passive"))
    )
    (net (code "122") (name "Net-(BOOT-Pad4)") (class "Default")
      (node (ref "BOOT") (pin "4") (pinfunction "4_4") (pintype "passive"))
      (node (ref "R41") (pin "1") (pintype "passive"))
    )
    (net (code "123") (name "Net-(U6-OSC_IN)") (class "Default")
      (node (ref "C48") (pin "2") (pintype "passive"))
      (node (ref "R31") (pin "2") (pintype "passive"))
      (node (ref "U6") (pin "23") (pinfunction "OSC_IN_23") (pintype "passive"))
      (node (ref "Y4") (pin "2") (pinfunction "OSC2_2") (pintype "passive"))
    )
    (net (code "124") (name "Net-(U6-OSC_OUT)") (class "Default")
      (node (ref "C47") (pin "2") (pintype "passive"))
      (node (ref "R31") (pin "1") (pintype "passive"))
      (node (ref "U6") (pin "24") (pinfunction "OSC_OUT_24") (pintype "passive"))
      (node (ref "Y4") (pin "1") (pinfunction "OSC1_1") (pintype "passive"))
    )
    (net (code "125") (name "Net-(U6-PC14-OSC32_IN)") (class "Default")
      (node (ref "C44") (pin "2") (pintype "passive"))
      (node (ref "U6") (pin "8") (pinfunction "PC14-OSC32_IN_8") (pintype "passive"))
      (node (ref "Y3") (pin "1") (pinfunction "OSC1_1") (pintype "passive"))
    )
    (net (code "126") (name "Net-(U6-PC15-OSC32_OUT)") (class "Default")
      (node (ref "C45") (pin "2") (pintype "passive"))
      (node (ref "U6") (pin "9") (pinfunction "PC15-OSC32_OUT_9") (pintype "passive"))
      (node (ref "Y3") (pin "2") (pinfunction "OSC2_2") (pintype "passive"))
    )
    (net (code "127") (name "Net-(U6-VBAT)") (class "Default")
      (node (ref "D1") (pin "2") (pintype "passive"))
      (node (ref "D2") (pin "2") (pintype "passive"))
      (node (ref "U6") (pin "6") (pinfunction "VBAT_6") (pintype "passive"))
    )
    (net (code "128") (name "Net-(U6-VDDA)") (class "Default")
      (node (ref "C49") (pin "2") (pintype "passive"))
      (node (ref "C50") (pin "2") (pintype "passive"))
      (node (ref "R33") (pin "1") (pintype "passive"))
      (node (ref "U6") (pin "33") (pinfunction "VDDA_33") (pintype "passive"))
    )
    (net (code "129") (name "VCC3.3") (class "Default")
      (node (ref "2.4/2.8LCD") (pin "22") (pinfunction "GND_22") (pintype "passive"))
      (node (ref "2.4/2.8LCD") (pin "24") (pinfunction "VDD3.3_24") (pintype "passive"))
      (node (ref "2.4/2.8LCD") (pin "25") (pinfunction "VDD3.3_25") (pintype "passive"))
      (node (ref "BOOT") (pin "1") (pinfunction "1_1") (pintype "passive"))
      (node (ref "BOOT") (pin "2") (pinfunction "2_2") (pintype "passive"))
      (node (ref "C41") (pin "2") (pintype "passive"))
      (node (ref "C43") (pin "1") (pintype "passive"))
      (node (ref "JTAG") (pin "1") (pinfunction "VDD_1") (pintype "passive"))
      (node (ref "JTAG") (pin "2") (pinfunction "VDD_2") (pintype "passive"))
      (node (ref "OLED") (pin "2") (pinfunction "2_2") (pintype "passive"))
      (node (ref "R32") (pin "2") (pintype "passive"))
      (node (ref "R33") (pin "2") (pintype "passive"))
      (node (ref "R34") (pin "1") (pintype "passive"))
      (node (ref "R35") (pin "1") (pintype "passive"))
      (node (ref "R36") (pin "1") (pintype "passive"))
      (node (ref "R37") (pin "1") (pintype "passive"))
      (node (ref "R38") (pin "1") (pintype "passive"))
      (node (ref "R39") (pin "1") (pintype "passive"))
    )
    (net (code "130") (name "VCC3.3M") (class "Default")
      (node (ref "C39") (pin "2") (pintype "passive"))
      (node (ref "C40") (pin "2") (pintype "passive"))
      (node (ref "C52") (pin "1") (pintype "passive"))
      (node (ref "C53") (pin "1") (pintype "passive"))
      (node (ref "C54") (pin "1") (pintype "passive"))
      (node (ref "C55") (pin "1") (pintype "passive"))
      (node (ref "C56") (pin "1") (pintype "passive"))
      (node (ref "C57") (pin "1") (pintype "passive"))
      (node (ref "C58") (pin "1") (pintype "passive"))
      (node (ref "C59") (pin "1") (pintype "passive"))
      (node (ref "C60") (pin "1") (pintype "passive"))
      (node (ref "C61") (pin "1") (pintype "passive"))
      (node (ref "C62") (pin "1") (pintype "passive"))
      (node (ref "D1") (pin "1") (pintype "passive"))
      (node (ref "R30") (pin "2") (pintype "passive"))
      (node (ref "R37") (pin "2") (pintype "passive"))
      (node (ref "R38") (pin "2") (pintype "passive"))
      (node (ref "U5") (pin "11") (pinfunction "VDD_11") (pintype "passive"))
      (node (ref "U5") (pin "33") (pinfunction "VDD_33") (pintype "passive"))
      (node (ref "U6") (pin "108") (pinfunction "VDD_108") (pintype "passive"))
      (node (ref "U6") (pin "121") (pinfunction "VDD_121") (pintype "passive"))
      (node (ref "U6") (pin "131") (pinfunction "VDD_131") (pintype "passive"))
      (node (ref "U6") (pin "144") (pinfunction "VDD_144") (pintype "passive"))
      (node (ref "U6") (pin "17") (pinfunction "VDD_17") (pintype "passive"))
      (node (ref "U6") (pin "39") (pinfunction "VDD_39") (pintype "passive"))
      (node (ref "U6") (pin "52") (pinfunction "VDD_52") (pintype "passive"))
      (node (ref "U6") (pin "62") (pinfunction "VDD_62") (pintype "passive"))
      (node (ref "U6") (pin "72") (pinfunction "VDD_72") (pintype "passive"))
      (node (ref "U6") (pin "84") (pinfunction "VDD_84") (pintype "passive"))
      (node (ref "U6") (pin "95") (pinfunction "VDD_95") (pintype "passive"))
    )
    (net (code "131") (name "VDDA") (class "Default")
      (node (ref "P7") (pin "2") (pinfunction "2_2") (pintype "passive"))
    )
    (net (code "132") (name "unconnected-(2.4/2.8LCD-MO-Pad32)") (class "Default")
      (node (ref "2.4/2.8LCD") (pin "32") (pinfunction "MO_32") (pintype "passive"))
    )
    (net (code "133") (name "unconnected-(JTAG-NC-Pad11)") (class "Default")
      (node (ref "JTAG") (pin "11") (pinfunction "NC_11") (pintype "passive"))
    )
    (net (code "134") (name "unconnected-(JTAG-NC-Pad17)") (class "Default")
      (node (ref "JTAG") (pin "17") (pinfunction "NC_17") (pintype "passive"))
    )
    (net (code "135") (name "unconnected-(JTAG-NC-Pad19)") (class "Default")
      (node (ref "JTAG") (pin "19") (pinfunction "NC_19") (pintype "passive"))
    )
    (net (code "136") (name "unconnected-(U6-NC-Pad106)") (class "Default")
      (node (ref "U6") (pin "106") (pinfunction "NC_106") (pintype "passive"))
    )
  )
)
